# usb-volume.net
KiCad netlist of a schematic drawn in EAGLE
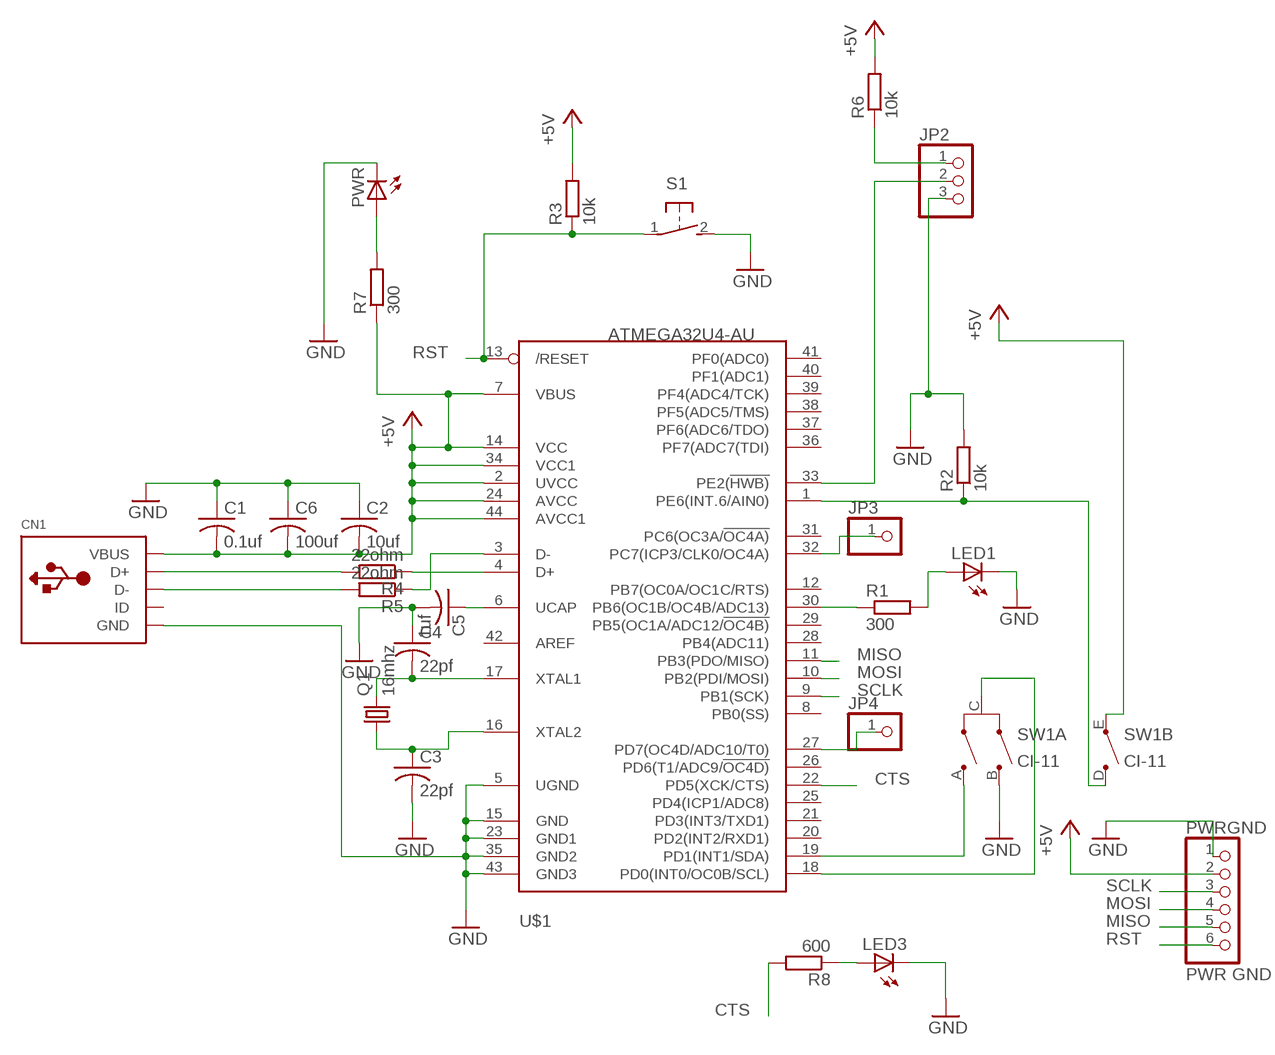
[diagram p0: schematic, sheet 1]

(export (version "E")
  (design (tool "Eeschema 10.0.6"))
  (components
    (comp (ref "C1")
      (value "0.1uf")
      (footprint "eagle-import:C0805")
      (libsource (lib "eagle-import") (part "C-USC0805"))
    )
    (comp (ref "C2")
      (value "10uf")
      (footprint "eagle-import:C0805")
      (libsource (lib "eagle-import") (part "C-USC0805"))
    )
    (comp (ref "C3")
      (value "22pf")
      (footprint "eagle-import:C025-025X050")
      (libsource (lib "eagle-import") (part "C-US025-025X050"))
    )
    (comp (ref "C4")
      (value "22pf")
      (footprint "eagle-import:C025-025X050")
      (libsource (lib "eagle-import") (part "C-US025-025X050"))
    )
    (comp (ref "C5")
      (value "1uf")
      (footprint "eagle-import:C0805")
      (libsource (lib "eagle-import") (part "C-USC0805"))
    )
    (comp (ref "C6")
      (value "100uf")
      (footprint "eagle-import:C0805")
      (libsource (lib "eagle-import") (part "C-USC0805"))
    )
    (comp (ref "CN1")
      (value "USBMINIB")
      (footprint "eagle-import:USB-MINIB")
      (libsource (lib "eagle-import") (part "USBMINIB"))
    )
    (comp (ref "JP2")
      (value "PINHD-1X3")
      (footprint "eagle-import:1X03")
      (libsource (lib "eagle-import") (part "PINHD-1X3"))
    )
    (comp (ref "JP3")
      (value "PINHD-1X1")
      (footprint "eagle-import:1X01")
      (libsource (lib "eagle-import") (part "PINHD-1X1"))
    )
    (comp (ref "JP4")
      (value "PINHD-1X1")
      (footprint "eagle-import:1X01")
      (libsource (lib "eagle-import") (part "PINHD-1X1"))
    )
    (comp (ref "LED1")
      (value "LED5MM")
      (footprint "eagle-import:LED5MM")
      (libsource (lib "eagle-import") (part "LED5MM"))
    )
    (comp (ref "LED3")
      (value "LEDCHIPLED_1206")
      (footprint "eagle-import:CHIPLED_1206")
      (libsource (lib "eagle-import") (part "LEDCHIPLED_1206"))
    )
    (comp (ref "PWR")
      (value "LEDCHIPLED_1206")
      (footprint "eagle-import:CHIPLED_1206")
      (libsource (lib "eagle-import") (part "LEDCHIPLED_1206"))
    )
    (comp (ref "PWRGND")
      (value "PWR GND")
      (footprint "eagle-import:1X06")
      (libsource (lib "eagle-import") (part "PINHD-1X6"))
    )
    (comp (ref "Q1")
      (value "16mhz")
      (footprint "eagle-import:HC49_S")
      (libsource (lib "eagle-import") (part "CRYSTALHC49S"))
    )
    (comp (ref "R1")
      (value "300")
      (footprint "eagle-import:R0805")
      (libsource (lib "eagle-import") (part "R-EU_R0805"))
    )
    (comp (ref "R2")
      (value "10k")
      (footprint "eagle-import:R0805")
      (libsource (lib "eagle-import") (part "R-EU_R0805"))
    )
    (comp (ref "R3")
      (value "10k")
      (footprint "eagle-import:R0805")
      (libsource (lib "eagle-import") (part "R-EU_R0805"))
    )
    (comp (ref "R4")
      (value "22ohm")
      (footprint "eagle-import:R0805")
      (libsource (lib "eagle-import") (part "R-EU_R0805"))
    )
    (comp (ref "R5")
      (value "22ohm")
      (footprint "eagle-import:R0805")
      (libsource (lib "eagle-import") (part "R-EU_R0805"))
    )
    (comp (ref "R6")
      (value "10k")
      (footprint "eagle-import:R0805")
      (libsource (lib "eagle-import") (part "R-EU_R0805"))
    )
    (comp (ref "R7")
      (value "300")
      (footprint "eagle-import:R0805")
      (libsource (lib "eagle-import") (part "R-EU_R0805"))
    )
    (comp (ref "R8")
      (value "600")
      (footprint "eagle-import:R0805")
      (libsource (lib "eagle-import") (part "R-EU_R0805"))
    )
    (comp (ref "S1")
      (value "31-XX")
      (footprint "eagle-import:B3F-31XX")
      (libsource (lib "eagle-import") (part "31-XX"))
    )
    (comp (ref "SW1")
      (value "CI-11")
      (footprint "eagle-import:CI-11")
      (libsource (lib "eagle-import") (part "CI-11"))
    )
    (comp (ref "U$1")
      (value "ATMEGA32U4-AU")
      (footprint "eagle-import:TQFP44")
      (libsource (lib "eagle-import") (part "ATMEGA32U4-AU"))
    )
  )
  (nets
    (net (code "1") (name "+5V") (class "Default")
      (node (ref "C1") (pin "2") (pinfunction "2_2") (pintype "passive"))
      (node (ref "C2") (pin "2") (pinfunction "2_2") (pintype "passive"))
      (node (ref "C6") (pin "2") (pinfunction "2_2") (pintype "passive"))
      (node (ref "CN1") (pin "VBUS") (pinfunction "VBUS_VBUS") (pintype "power_in"))
      (node (ref "PWRGND") (pin "2") (pinfunction "2_2") (pintype "passive"))
      (node (ref "R3") (pin "2") (pinfunction "2_2") (pintype "passive"))
      (node (ref "R6") (pin "2") (pinfunction "2_2") (pintype "passive"))
      (node (ref "R7") (pin "1") (pinfunction "1_1") (pintype "passive"))
      (node (ref "SW1") (pin "E") (pinfunction "E_E") (pintype "passive"))
      (node (ref "U$1") (pin "14") (pinfunction "VCC_14") (pintype "bidirectional"))
      (node (ref "U$1") (pin "2") (pinfunction "UVCC_2") (pintype "bidirectional"))
      (node (ref "U$1") (pin "24") (pinfunction "AVCC_24") (pintype "bidirectional"))
      (node (ref "U$1") (pin "34") (pinfunction "VCC1_34") (pintype "bidirectional"))
      (node (ref "U$1") (pin "44") (pinfunction "AVCC1_44") (pintype "bidirectional"))
      (node (ref "U$1") (pin "7") (pinfunction "VBUS_7") (pintype "bidirectional"))
    )
    (net (code "2") (name "/CTS") (class "Default")
      (node (ref "R8") (pin "2") (pinfunction "2_2") (pintype "passive"))
      (node (ref "U$1") (pin "22") (pinfunction "PD5(XCK/CTS)_22") (pintype "bidirectional"))
    )
    (net (code "3") (name "/MISO") (class "Default")
      (node (ref "PWRGND") (pin "5") (pinfunction "5_5") (pintype "passive"))
      (node (ref "U$1") (pin "11") (pinfunction "PB3(PDO/MISO)_11") (pintype "bidirectional"))
    )
    (net (code "4") (name "/MOSI") (class "Default")
      (node (ref "PWRGND") (pin "4") (pinfunction "4_4") (pintype "passive"))
      (node (ref "U$1") (pin "10") (pinfunction "PB2(PDI/MOSI)_10") (pintype "bidirectional"))
    )
    (net (code "5") (name "/RST") (class "Default")
      (node (ref "PWRGND") (pin "6") (pinfunction "6_6") (pintype "passive"))
      (node (ref "R3") (pin "1") (pinfunction "1_1") (pintype "passive"))
      (node (ref "S1") (pin "1") (pinfunction "P_1") (pintype "passive"))
      (node (ref "U$1") (pin "13") (pinfunction "/RESET_13") (pintype "bidirectional"))
    )
    (net (code "6") (name "/SCLK") (class "Default")
      (node (ref "PWRGND") (pin "3") (pinfunction "3_3") (pintype "passive"))
      (node (ref "U$1") (pin "9") (pinfunction "PB1(SCK)_9") (pintype "bidirectional"))
    )
    (net (code "7") (name "GND") (class "Default")
      (node (ref "C1") (pin "1") (pinfunction "1_1") (pintype "passive"))
      (node (ref "C2") (pin "1") (pinfunction "1_1") (pintype "passive"))
      (node (ref "C3") (pin "2") (pinfunction "2_2") (pintype "passive"))
      (node (ref "C4") (pin "1") (pinfunction "1_1") (pintype "passive"))
      (node (ref "C5") (pin "2") (pinfunction "2_2") (pintype "passive"))
      (node (ref "C6") (pin "1") (pinfunction "1_1") (pintype "passive"))
      (node (ref "CN1") (pin "GND") (pinfunction "GND_GND") (pintype "power_in"))
      (node (ref "JP2") (pin "3") (pinfunction "3_3") (pintype "passive"))
      (node (ref "LED1") (pin "K") (pinfunction "C_K") (pintype "passive"))
      (node (ref "LED3") (pin "C") (pinfunction "C_C") (pintype "passive"))
      (node (ref "PWR") (pin "C") (pinfunction "C_C") (pintype "passive"))
      (node (ref "PWRGND") (pin "1") (pinfunction "1_1") (pintype "passive"))
      (node (ref "R2") (pin "2") (pinfunction "2_2") (pintype "passive"))
      (node (ref "S1") (pin "2") (pinfunction "S_2") (pintype "passive"))
      (node (ref "SW1") (pin "B") (pinfunction "B_B") (pintype "passive"))
      (node (ref "U$1") (pin "15") (pinfunction "GND_15") (pintype "bidirectional"))
      (node (ref "U$1") (pin "23") (pinfunction "GND1_23") (pintype "bidirectional"))
      (node (ref "U$1") (pin "35") (pinfunction "GND2_35") (pintype "bidirectional"))
      (node (ref "U$1") (pin "43") (pinfunction "GND3_43") (pintype "bidirectional"))
      (node (ref "U$1") (pin "5") (pinfunction "UGND_5") (pintype "bidirectional"))
    )
    (net (code "8") (name "Net-(CN1-PadD+)") (class "Default")
      (node (ref "CN1") (pin "D+") (pinfunction "D+_D+") (pintype "bidirectional"))
      (node (ref "R4") (pin "2") (pinfunction "2_2") (pintype "passive"))
    )
    (net (code "9") (name "Net-(CN1-PadD-)") (class "Default")
      (node (ref "CN1") (pin "D-") (pinfunction "D-_D-") (pintype "bidirectional"))
      (node (ref "R5") (pin "2") (pinfunction "2_2") (pintype "passive"))
    )
    (net (code "10") (name "Net-(JP2-Pad1)") (class "Default")
      (node (ref "JP2") (pin "1") (pinfunction "1_1") (pintype "passive"))
      (node (ref "R6") (pin "1") (pinfunction "1_1") (pintype "passive"))
    )
    (net (code "11") (name "Net-(LED1-PadA)") (class "Default")
      (node (ref "LED1") (pin "A") (pinfunction "A_A") (pintype "passive"))
      (node (ref "R1") (pin "2") (pinfunction "2_2") (pintype "passive"))
    )
    (net (code "12") (name "Net-(LED3-PadA)") (class "Default")
      (node (ref "LED3") (pin "A") (pinfunction "A_A") (pintype "passive"))
      (node (ref "R8") (pin "1") (pinfunction "1_1") (pintype "passive"))
    )
    (net (code "13") (name "Net-(PWR-PadA)") (class "Default")
      (node (ref "PWR") (pin "A") (pinfunction "A_A") (pintype "passive"))
      (node (ref "R7") (pin "2") (pinfunction "2_2") (pintype "passive"))
    )
    (net (code "14") (name "Net-(U$1-D+)") (class "Default")
      (node (ref "R4") (pin "1") (pinfunction "1_1") (pintype "passive"))
      (node (ref "U$1") (pin "4") (pinfunction "D+_4") (pintype "bidirectional"))
    )
    (net (code "15") (name "Net-(U$1-D-)") (class "Default")
      (node (ref "R5") (pin "1") (pinfunction "1_1") (pintype "passive"))
      (node (ref "U$1") (pin "3") (pinfunction "D-_3") (pintype "bidirectional"))
    )
    (net (code "16") (name "Net-(U$1-PB6(OC1B{slash}OC4B{slash}ADC13))") (class "Default")
      (node (ref "R1") (pin "1") (pinfunction "1_1") (pintype "passive"))
      (node (ref "U$1") (pin "30") (pinfunction "PB6(OC1B/OC4B/ADC13)_30") (pintype "bidirectional"))
    )
    (net (code "17") (name "Net-(U$1-PC7(ICP3{slash}CLK0{slash}OC4A))") (class "Default")
      (node (ref "JP3") (pin "1") (pinfunction "1_1") (pintype "passive"))
      (node (ref "U$1") (pin "32") (pinfunction "PC7(ICP3/CLK0/OC4A)_32") (pintype "bidirectional"))
    )
    (net (code "18") (name "Net-(U$1-PD0(INT0{slash}OC0B{slash}SCL))") (class "Default")
      (node (ref "SW1") (pin "C") (pinfunction "C_C") (pintype "passive"))
      (node (ref "U$1") (pin "18") (pinfunction "PD0(INT0/OC0B/SCL)_18") (pintype "bidirectional"))
    )
    (net (code "19") (name "Net-(U$1-PD1(INT1{slash}SDA))") (class "Default")
      (node (ref "SW1") (pin "A") (pinfunction "A_A") (pintype "passive"))
      (node (ref "U$1") (pin "19") (pinfunction "PD1(INT1/SDA)_19") (pintype "bidirectional"))
    )
    (net (code "20") (name "Net-(U$1-PD7(OC4D{slash}ADC10{slash}T0))") (class "Default")
      (node (ref "JP4") (pin "1") (pinfunction "1_1") (pintype "passive"))
      (node (ref "U$1") (pin "27") (pinfunction "PD7(OC4D/ADC10/T0)_27") (pintype "bidirectional"))
    )
    (net (code "21") (name "Net-(U$1-PE2(~{HWB}))") (class "Default")
      (node (ref "JP2") (pin "2") (pinfunction "2_2") (pintype "passive"))
      (node (ref "U$1") (pin "33") (pinfunction "PE2(~{HWB})_33") (pintype "bidirectional"))
    )
    (net (code "22") (name "Net-(U$1-PE6(INT.6{slash}AIN0))") (class "Default")
      (node (ref "R2") (pin "1") (pinfunction "1_1") (pintype "passive"))
      (node (ref "SW1") (pin "D") (pinfunction "D_D") (pintype "passive"))
      (node (ref "U$1") (pin "1") (pinfunction "PE6(INT.6/AIN0)_1") (pintype "bidirectional"))
    )
    (net (code "23") (name "Net-(U$1-UCAP)") (class "Default")
      (node (ref "C5") (pin "1") (pinfunction "1_1") (pintype "passive"))
      (node (ref "U$1") (pin "6") (pinfunction "UCAP_6") (pintype "bidirectional"))
    )
    (net (code "24") (name "Net-(U$1-XTAL1)") (class "Default")
      (node (ref "C4") (pin "2") (pinfunction "2_2") (pintype "passive"))
      (node (ref "Q1") (pin "2") (pinfunction "2_2") (pintype "passive"))
      (node (ref "U$1") (pin "17") (pinfunction "XTAL1_17") (pintype "bidirectional"))
    )
    (net (code "25") (name "Net-(U$1-XTAL2)") (class "Default")
      (node (ref "C3") (pin "1") (pinfunction "1_1") (pintype "passive"))
      (node (ref "Q1") (pin "1") (pinfunction "1_1") (pintype "passive"))
      (node (ref "U$1") (pin "16") (pinfunction "XTAL2_16") (pintype "bidirectional"))
    )
    (net (code "26") (name "unconnected-(CN1-PadID)") (class "Default")
      (node (ref "CN1") (pin "ID") (pinfunction "ID_ID") (pintype "bidirectional"))
    )
    (net (code "27") (name "unconnected-(U$1-AREF-Pad42)") (class "Default")
      (node (ref "U$1") (pin "42") (pinfunction "AREF_42") (pintype "bidirectional"))
    )
    (net (code "28") (name "unconnected-(U$1-PB0(SS)-Pad8)") (class "Default")
      (node (ref "U$1") (pin "8") (pinfunction "PB0(SS)_8") (pintype "bidirectional"))
    )
    (net (code "29") (name "unconnected-(U$1-PB4(ADC11)-Pad28)") (class "Default")
      (node (ref "U$1") (pin "28") (pinfunction "PB4(ADC11)_28") (pintype "bidirectional"))
    )
    (net (code "30") (name "unconnected-(U$1-PB5(OC1A{slash}ADC12{slash}~{OC4B})-Pad29)") (class "Default")
      (node (ref "U$1") (pin "29") (pinfunction "PB5(OC1A/ADC12/~{OC4B})_29") (pintype "bidirectional"))
    )
    (net (code "31") (name "unconnected-(U$1-PB7(OC0A{slash}OC1C{slash}RTS)-Pad12)") (class "Default")
      (node (ref "U$1") (pin "12") (pinfunction "PB7(OC0A/OC1C/RTS)_12") (pintype "bidirectional"))
    )
    (net (code "32") (name "unconnected-(U$1-PC6(OC3A{slash}~{OC4A})-Pad31)") (class "Default")
      (node (ref "U$1") (pin "31") (pinfunction "PC6(OC3A/~{OC4A})_31") (pintype "bidirectional"))
    )
    (net (code "33") (name "unconnected-(U$1-PD2(INT2{slash}RXD1)-Pad20)") (class "Default")
      (node (ref "U$1") (pin "20") (pinfunction "PD2(INT2/RXD1)_20") (pintype "bidirectional"))
    )
    (net (code "34") (name "unconnected-(U$1-PD3(INT3{slash}TXD1)-Pad21)") (class "Default")
      (node (ref "U$1") (pin "21") (pinfunction "PD3(INT3/TXD1)_21") (pintype "bidirectional"))
    )
    (net (code "35") (name "unconnected-(U$1-PD4(ICP1{slash}ADC8)-Pad25)") (class "Default")
      (node (ref "U$1") (pin "25") (pinfunction "PD4(ICP1/ADC8)_25") (pintype "bidirectional"))
    )
    (net (code "36") (name "unconnected-(U$1-PD6(T1{slash}ADC9{slash}~{OC4D})-Pad26)") (class "Default")
      (node (ref "U$1") (pin "26") (pinfunction "PD6(T1/ADC9/~{OC4D})_26") (pintype "bidirectional"))
    )
    (net (code "37") (name "unconnected-(U$1-PF0(ADC0)-Pad41)") (class "Default")
      (node (ref "U$1") (pin "41") (pinfunction "PF0(ADC0)_41") (pintype "bidirectional"))
    )
    (net (code "38") (name "unconnected-(U$1-PF1(ADC1)-Pad40)") (class "Default")
      (node (ref "U$1") (pin "40") (pinfunction "PF1(ADC1)_40") (pintype "bidirectional"))
    )
    (net (code "39") (name "unconnected-(U$1-PF4(ADC4{slash}TCK)-Pad39)") (class "Default")
      (node (ref "U$1") (pin "39") (pinfunction "PF4(ADC4/TCK)_39") (pintype "bidirectional"))
    )
    (net (code "40") (name "unconnected-(U$1-PF5(ADC5{slash}TMS)-Pad38)") (class "Default")
      (node (ref "U$1") (pin "38") (pinfunction "PF5(ADC5/TMS)_38") (pintype "bidirectional"))
    )
    (net (code "41") (name "unconnected-(U$1-PF6(ADC6{slash}TDO)-Pad37)") (class "Default")
      (node (ref "U$1") (pin "37") (pinfunction "PF6(ADC6/TDO)_37") (pintype "bidirectional"))
    )
    (net (code "42") (name "unconnected-(U$1-PF7(ADC7(TDI)-Pad36)") (class "Default")
      (node (ref "U$1") (pin "36") (pinfunction "PF7(ADC7(TDI)_36") (pintype "bidirectional"))
    )
  )
)
